# max30105_iiT.net
KiCad netlist of a schematic drawn in EAGLE
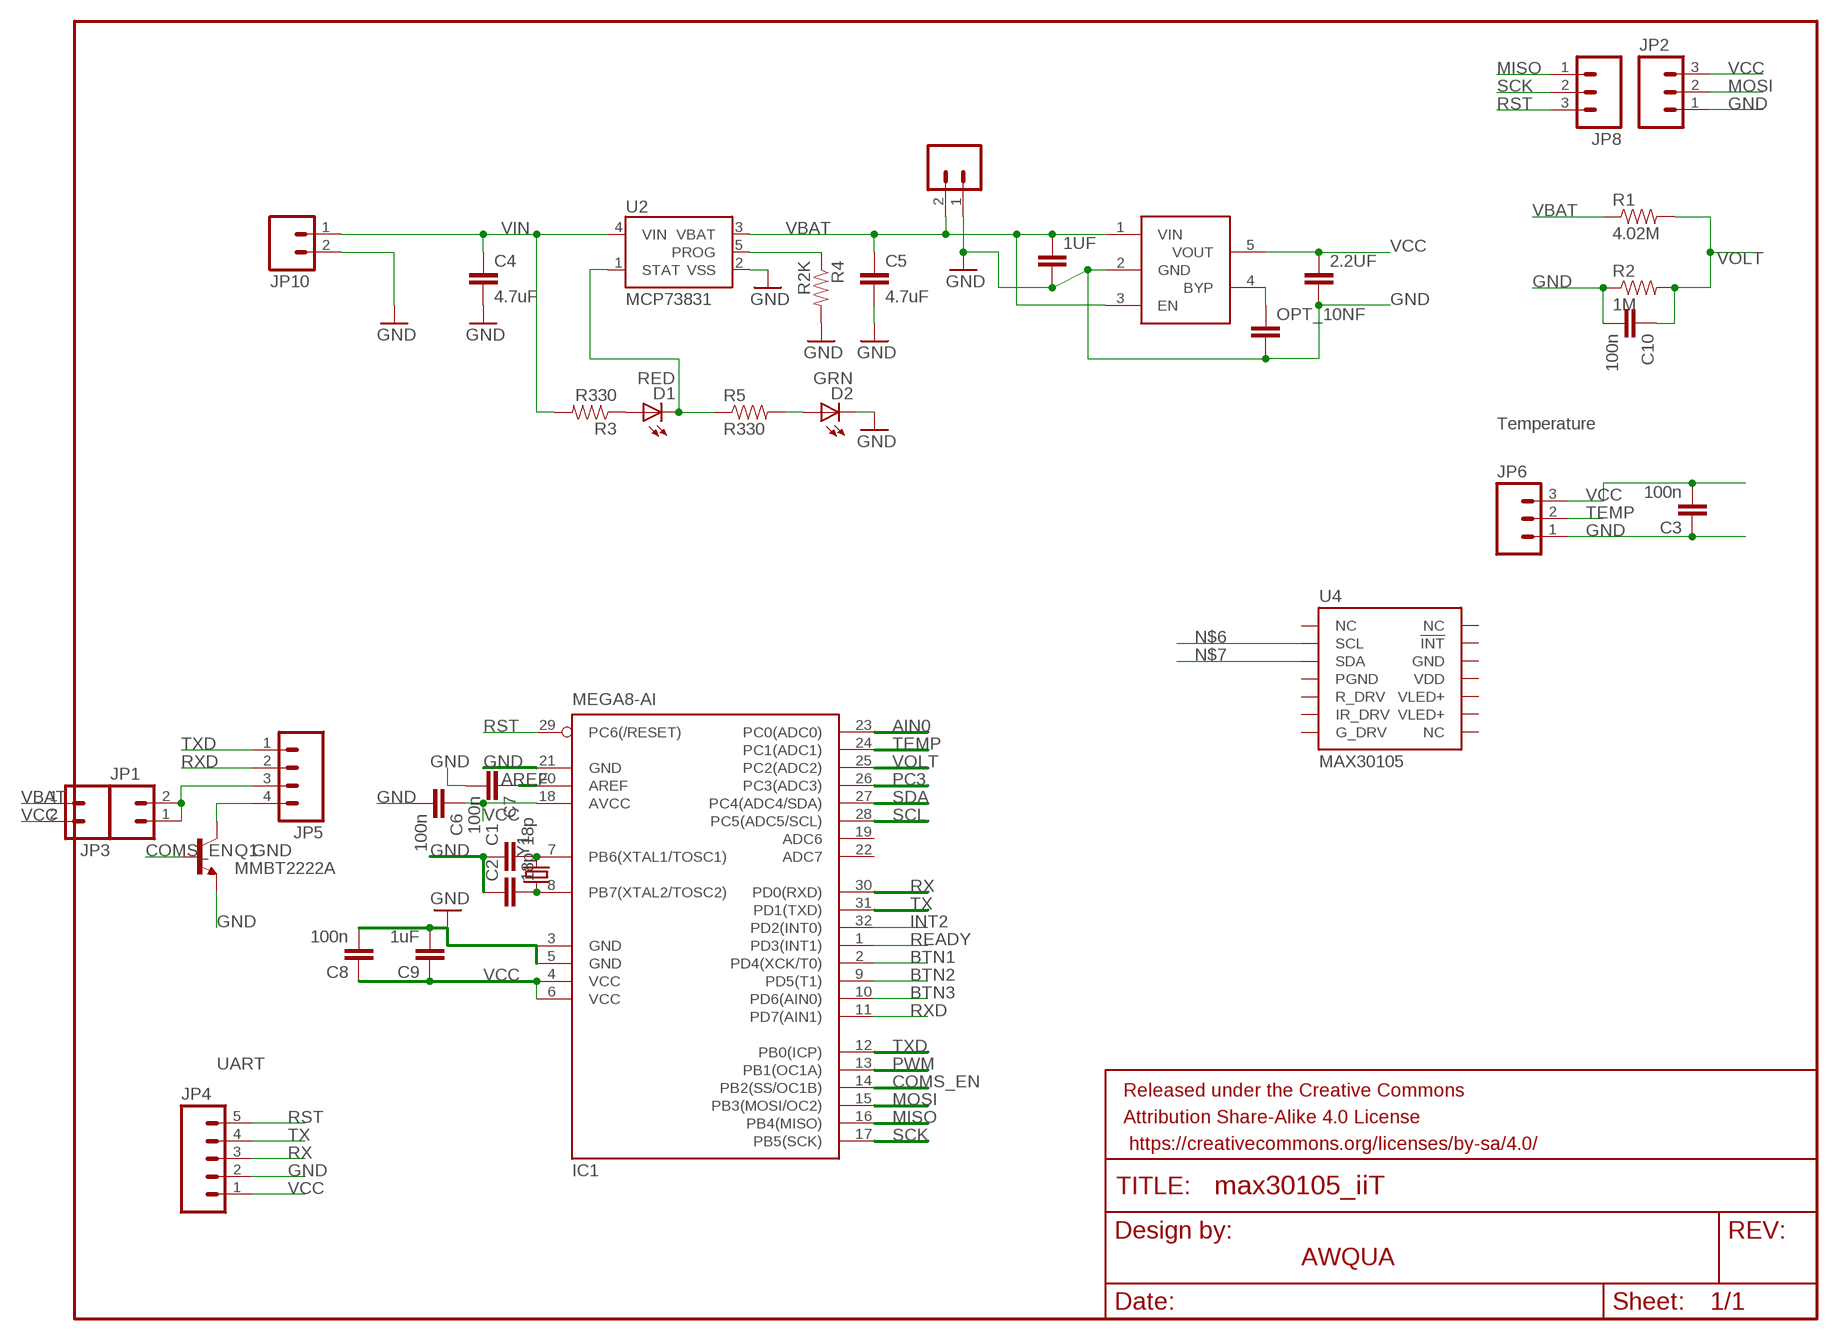
[diagram p0: schematic, sheet 1]

(export (version "E")
  (design (tool "Eeschema 10.0.6"))
  (components
    (comp (ref "1UF")
      (value "CAP0603-CAP")
      (footprint "eagle-import:0603-CAP")
      (libsource (lib "eagle-import") (part "SparkFun-Passives_CAP0603-CAP"))
    )
    (comp (ref "2.2UF")
      (value "CAP0603-CAP")
      (footprint "eagle-import:0603-CAP")
      (libsource (lib "eagle-import") (part "SparkFun-Passives_CAP0603-CAP"))
    )
    (comp (ref "C1")
      (value "18p")
      (footprint "eagle-import:0603-CAP")
      (libsource (lib "eagle-import") (part "CAP0603-CAP"))
    )
    (comp (ref "C2")
      (value "18p")
      (footprint "eagle-import:0603-CAP")
      (libsource (lib "eagle-import") (part "CAP0603-CAP"))
    )
    (comp (ref "C3")
      (value "100n")
      (footprint "eagle-import:0603-CAP")
      (libsource (lib "eagle-import") (part "CAP0603-CAP"))
    )
    (comp (ref "C4")
      (value "4.7uF")
      (footprint "eagle-import:0402-CAP")
      (libsource (lib "eagle-import") (part "CAP0402-CAP"))
    )
    (comp (ref "C5")
      (value "4.7uF")
      (footprint "eagle-import:0402-CAP")
      (libsource (lib "eagle-import") (part "CAP0402-CAP"))
    )
    (comp (ref "C6")
      (value "100n")
      (footprint "eagle-import:0603-CAP")
      (libsource (lib "eagle-import") (part "CAP0603-CAP"))
    )
    (comp (ref "C7")
      (value "100n")
      (footprint "eagle-import:0603-CAP")
      (libsource (lib "eagle-import") (part "CAP0603-CAP"))
    )
    (comp (ref "C8")
      (value "100n")
      (footprint "eagle-import:0603-CAP")
      (libsource (lib "eagle-import") (part "CAP0603-CAP"))
    )
    (comp (ref "C9")
      (value "1uF")
      (footprint "eagle-import:0603-CAP")
      (libsource (lib "eagle-import") (part "CAP0603-CAP"))
    )
    (comp (ref "C10")
      (value "100n")
      (footprint "eagle-import:0603-CAP")
      (libsource (lib "eagle-import") (part "CAP0603-CAP"))
    )
    (comp (ref "D1")
      (value "RED")
      (footprint "eagle-import:LED-0603")
      (libsource (lib "eagle-import") (part "LED0603"))
    )
    (comp (ref "D2")
      (value "GRN")
      (footprint "eagle-import:LED-0603")
      (libsource (lib "eagle-import") (part "LED0603"))
    )
    (comp (ref "FRAME1")
      (value "FRAME-LETTER")
      (footprint "eagle-import:CREATIVE_COMMONS")
      (libsource (lib "eagle-import") (part "FRAME-LETTER"))
    )
    (comp (ref "IC1")
      (value "MEGA8-AI")
      (footprint "eagle-import:TQFP32-08")
      (fields (field (name "MPN") "ATMEGA8-16AU"))
      (libsource (lib "eagle-import") (part "MEGA8-AI"))
    )
    (comp (ref "JP1")
      (value "M02PTH")
      (footprint "eagle-import:1X02")
      (libsource (lib "eagle-import") (part "SparkFun-Connectors_M02PTH"))
    )
    (comp (ref "JP2")
      (value "M03PTH")
      (footprint "eagle-import:1X03")
      (libsource (lib "eagle-import") (part "M03PTH"))
    )
    (comp (ref "JP3")
      (value "M02PTH")
      (footprint "eagle-import:1X02")
      (libsource (lib "eagle-import") (part "SparkFun-Connectors_M02PTH"))
    )
    (comp (ref "JP4")
      (value "M05PTH")
      (footprint "eagle-import:1X05")
      (libsource (lib "eagle-import") (part "M05PTH"))
    )
    (comp (ref "JP5")
      (value "M04PTH")
      (footprint "eagle-import:1X04")
      (libsource (lib "eagle-import") (part "M04PTH"))
    )
    (comp (ref "JP6")
      (value "M03PTH")
      (footprint "eagle-import:1X03")
      (libsource (lib "eagle-import") (part "M03PTH"))
    )
    (comp (ref "JP7")
      (value "LiPo Battery")
      (footprint "eagle-import:JST-2-SMD")
      (libsource (lib "eagle-import") (part "M02-JST-2MM-SMT"))
    )
    (comp (ref "JP8")
      (value "M03PTH")
      (footprint "eagle-import:1X03")
      (libsource (lib "eagle-import") (part "M03PTH"))
    )
    (comp (ref "JP10")
      (value "M02PTH")
      (footprint "eagle-import:1X02")
      (libsource (lib "eagle-import") (part "SparkFun-Connectors_M02PTH"))
    )
    (comp (ref "OPT_10NF")
      (value "CAP0603-CAP")
      (footprint "eagle-import:0603-CAP")
      (libsource (lib "eagle-import") (part "SparkFun-Passives_CAP0603-CAP"))
    )
    (comp (ref "Q1")
      (value "MMBT2222A")
      (footprint "eagle-import:SOT23-3")
      (libsource (lib "eagle-import") (part "TRANSISTOR_NPNMMBT2222A"))
    )
    (comp (ref "R1")
      (value "4.02M")
      (footprint "eagle-import:0603-RES")
      (libsource (lib "eagle-import") (part "RESISTOR0603"))
    )
    (comp (ref "R2")
      (value "1M")
      (footprint "eagle-import:0603-RES")
      (libsource (lib "eagle-import") (part "RESISTOR0603"))
    )
    (comp (ref "R3")
      (value "R330")
      (footprint "eagle-import:0402-RES")
      (libsource (lib "eagle-import") (part "RESISTOR0402-RES"))
    )
    (comp (ref "R4")
      (value "R2K")
      (footprint "eagle-import:0402-RES")
      (libsource (lib "eagle-import") (part "RESISTOR0402-RES"))
    )
    (comp (ref "R5")
      (value "R330")
      (footprint "eagle-import:0402-RES")
      (libsource (lib "eagle-import") (part "RESISTOR0402-RES"))
    )
    (comp (ref "U$6")
      (value "LP2985")
      (footprint "eagle-import:LP2985")
      (libsource (lib "eagle-import") (part "LP2985"))
    )
    (comp (ref "U2")
      (value "MCP73831")
      (footprint "eagle-import:SOT23-5")
      (libsource (lib "eagle-import") (part "MCP73831"))
    )
    (comp (ref "U4")
      (value "MAX30105")
      (footprint "eagle-import:OLGA-14")
      (libsource (lib "eagle-import") (part "MAX30105SMD"))
    )
    (comp (ref "Y1")
      (value "CRYSTAL5X3")
      (footprint "eagle-import:CRYSTAL-SMD-5X3")
      (libsource (lib "eagle-import") (part "CRYSTAL5X3"))
    )
  )
  (nets
    (net (code "1") (name "/AIN0") (class "Default")
      (node (ref "IC1") (pin "23") (pinfunction "PC0(ADC0)_23") (pintype "bidirectional"))
    )
    (net (code "2") (name "/AREF") (class "Default")
      (node (ref "C7") (pin "1") (pinfunction "1_1") (pintype "passive"))
      (node (ref "IC1") (pin "20") (pinfunction "AREF_20") (pintype "passive"))
    )
    (net (code "3") (name "/BTN1") (class "Default")
      (node (ref "IC1") (pin "2") (pinfunction "PD4(XCK/T0)_2") (pintype "bidirectional"))
    )
    (net (code "4") (name "/BTN2") (class "Default")
      (node (ref "IC1") (pin "9") (pinfunction "PD5(T1)_9") (pintype "bidirectional"))
    )
    (net (code "5") (name "/BTN3") (class "Default")
      (node (ref "IC1") (pin "10") (pinfunction "PD6(AIN0)_10") (pintype "bidirectional"))
    )
    (net (code "6") (name "/COMS_EN") (class "Default")
      (node (ref "IC1") (pin "14") (pinfunction "PB2(SS/OC1B)_14") (pintype "bidirectional"))
      (node (ref "Q1") (pin "1") (pinfunction "B_1") (pintype "passive"))
    )
    (net (code "7") (name "/INT2") (class "Default")
      (node (ref "IC1") (pin "32") (pinfunction "PD2(INT0)_32") (pintype "bidirectional"))
    )
    (net (code "8") (name "/MISO") (class "Default")
      (node (ref "IC1") (pin "16") (pinfunction "PB4(MISO)_16") (pintype "bidirectional"))
      (node (ref "JP8") (pin "1") (pinfunction "1_1") (pintype "passive"))
    )
    (net (code "9") (name "/MOSI") (class "Default")
      (node (ref "IC1") (pin "15") (pinfunction "PB3(MOSI/OC2)_15") (pintype "bidirectional"))
      (node (ref "JP2") (pin "2") (pinfunction "2_2") (pintype "passive"))
    )
    (net (code "10") (name "/N$6") (class "Default")
      (node (ref "U4") (pin "2") (pinfunction "SCL_2") (pintype "bidirectional"))
    )
    (net (code "11") (name "/N$7") (class "Default")
      (node (ref "U4") (pin "3") (pinfunction "SDA_3") (pintype "bidirectional"))
    )
    (net (code "12") (name "/PC3") (class "Default")
      (node (ref "IC1") (pin "26") (pinfunction "PC3(ADC3)_26") (pintype "bidirectional"))
    )
    (net (code "13") (name "/PWM") (class "Default")
      (node (ref "IC1") (pin "13") (pinfunction "PB1(OC1A)_13") (pintype "bidirectional"))
    )
    (net (code "14") (name "/READY") (class "Default")
      (node (ref "IC1") (pin "1") (pinfunction "PD3(INT1)_1") (pintype "bidirectional"))
    )
    (net (code "15") (name "/RST") (class "Default")
      (node (ref "IC1") (pin "29") (pinfunction "PC6(/RESET)_29") (pintype "bidirectional"))
      (node (ref "JP4") (pin "5") (pinfunction "5_5") (pintype "passive"))
      (node (ref "JP8") (pin "3") (pinfunction "3_3") (pintype "passive"))
    )
    (net (code "16") (name "/RX") (class "Default")
      (node (ref "IC1") (pin "30") (pinfunction "PD0(RXD)_30") (pintype "bidirectional"))
      (node (ref "JP4") (pin "3") (pinfunction "3_3") (pintype "passive"))
    )
    (net (code "17") (name "/RXD") (class "Default")
      (node (ref "IC1") (pin "11") (pinfunction "PD7(AIN1)_11") (pintype "bidirectional"))
      (node (ref "JP5") (pin "2") (pinfunction "2_2") (pintype "passive"))
    )
    (net (code "18") (name "/SCK") (class "Default")
      (node (ref "IC1") (pin "17") (pinfunction "PB5(SCK)_17") (pintype "bidirectional"))
      (node (ref "JP8") (pin "2") (pinfunction "2_2") (pintype "passive"))
    )
    (net (code "19") (name "/SCL") (class "Default")
      (node (ref "IC1") (pin "28") (pinfunction "PC5(ADC5/SCL)_28") (pintype "bidirectional"))
    )
    (net (code "20") (name "/SDA") (class "Default")
      (node (ref "IC1") (pin "27") (pinfunction "PC4(ADC4/SDA)_27") (pintype "bidirectional"))
    )
    (net (code "21") (name "/TEMP") (class "Default")
      (node (ref "IC1") (pin "24") (pinfunction "PC1(ADC1)_24") (pintype "bidirectional"))
      (node (ref "JP6") (pin "2") (pinfunction "2_2") (pintype "passive"))
    )
    (net (code "22") (name "/TX") (class "Default")
      (node (ref "IC1") (pin "31") (pinfunction "PD1(TXD)_31") (pintype "bidirectional"))
      (node (ref "JP4") (pin "4") (pinfunction "4_4") (pintype "passive"))
    )
    (net (code "23") (name "/TXD") (class "Default")
      (node (ref "IC1") (pin "12") (pinfunction "PB0(ICP)_12") (pintype "bidirectional"))
      (node (ref "JP5") (pin "1") (pinfunction "1_1") (pintype "passive"))
    )
    (net (code "24") (name "/VBAT") (class "Default")
      (node (ref "1UF") (pin "1") (pinfunction "1_1") (pintype "passive"))
      (node (ref "C5") (pin "1") (pinfunction "1_1") (pintype "passive"))
      (node (ref "JP3") (pin "1") (pinfunction "1_1") (pintype "passive"))
      (node (ref "JP7") (pin "2") (pinfunction "2_2") (pintype "passive"))
      (node (ref "R1") (pin "1") (pinfunction "1_1") (pintype "passive"))
      (node (ref "U$6") (pin "1") (pinfunction "VIN_1") (pintype "bidirectional"))
      (node (ref "U$6") (pin "3") (pinfunction "EN_3") (pintype "bidirectional"))
      (node (ref "U2") (pin "3") (pinfunction "VBAT_3") (pintype "power_in"))
    )
    (net (code "25") (name "/VCC") (class "Default")
      (node (ref "2.2UF") (pin "1") (pinfunction "1_1") (pintype "passive"))
      (node (ref "C3") (pin "2") (pinfunction "2_2") (pintype "passive"))
      (node (ref "C6") (pin "1") (pinfunction "1_1") (pintype "passive"))
      (node (ref "C8") (pin "1") (pinfunction "1_1") (pintype "passive"))
      (node (ref "C9") (pin "1") (pinfunction "1_1") (pintype "passive"))
      (node (ref "IC1") (pin "18") (pinfunction "AVCC_18") (pintype "power_in"))
      (node (ref "IC1") (pin "4") (pinfunction "VCC_4") (pintype "power_in"))
      (node (ref "IC1") (pin "6") (pinfunction "VCC_6") (pintype "power_in"))
      (node (ref "JP2") (pin "3") (pinfunction "3_3") (pintype "passive"))
      (node (ref "JP3") (pin "2") (pinfunction "2_2") (pintype "passive"))
      (node (ref "JP4") (pin "1") (pinfunction "1_1") (pintype "passive"))
      (node (ref "JP6") (pin "3") (pinfunction "3_3") (pintype "passive"))
      (node (ref "U$6") (pin "5") (pinfunction "VOUT_5") (pintype "bidirectional"))
    )
    (net (code "26") (name "/VIN") (class "Default")
      (node (ref "C4") (pin "1") (pinfunction "1_1") (pintype "passive"))
      (node (ref "JP10") (pin "1") (pinfunction "1_1") (pintype "passive"))
      (node (ref "R3") (pin "2") (pinfunction "2_2") (pintype "passive"))
      (node (ref "U2") (pin "4") (pinfunction "VIN_4") (pintype "power_in"))
    )
    (net (code "27") (name "/VOLT") (class "Default")
      (node (ref "C10") (pin "1") (pinfunction "1_1") (pintype "passive"))
      (node (ref "IC1") (pin "25") (pinfunction "PC2(ADC2)_25") (pintype "bidirectional"))
      (node (ref "R1") (pin "2") (pinfunction "2_2") (pintype "passive"))
      (node (ref "R2") (pin "2") (pinfunction "2_2") (pintype "passive"))
    )
    (net (code "28") (name "GND") (class "Default")
      (node (ref "1UF") (pin "2") (pinfunction "2_2") (pintype "passive"))
      (node (ref "2.2UF") (pin "2") (pinfunction "2_2") (pintype "passive"))
      (node (ref "C1") (pin "1") (pinfunction "1_1") (pintype "passive"))
      (node (ref "C10") (pin "2") (pinfunction "2_2") (pintype "passive"))
      (node (ref "C2") (pin "1") (pinfunction "1_1") (pintype "passive"))
      (node (ref "C3") (pin "1") (pinfunction "1_1") (pintype "passive"))
      (node (ref "C4") (pin "2") (pinfunction "2_2") (pintype "passive"))
      (node (ref "C5") (pin "2") (pinfunction "2_2") (pintype "passive"))
      (node (ref "C6") (pin "2") (pinfunction "2_2") (pintype "passive"))
      (node (ref "C7") (pin "2") (pinfunction "2_2") (pintype "passive"))
      (node (ref "C8") (pin "2") (pinfunction "2_2") (pintype "passive"))
      (node (ref "C9") (pin "2") (pinfunction "2_2") (pintype "passive"))
      (node (ref "D2") (pin "C") (pinfunction "C_C") (pintype "passive"))
      (node (ref "IC1") (pin "21") (pinfunction "GND_21") (pintype "power_in"))
      (node (ref "IC1") (pin "3") (pinfunction "GND_3") (pintype "power_in"))
      (node (ref "IC1") (pin "5") (pinfunction "GND_5") (pintype "power_in"))
      (node (ref "JP10") (pin "2") (pinfunction "2_2") (pintype "passive"))
      (node (ref "JP2") (pin "1") (pinfunction "1_1") (pintype "passive"))
      (node (ref "JP4") (pin "2") (pinfunction "2_2") (pintype "passive"))
      (node (ref "JP5") (pin "4") (pinfunction "4_4") (pintype "passive"))
      (node (ref "JP6") (pin "1") (pinfunction "1_1") (pintype "passive"))
      (node (ref "JP7") (pin "1") (pinfunction "1_1") (pintype "passive"))
      (node (ref "OPT_10NF") (pin "2") (pinfunction "2_2") (pintype "passive"))
      (node (ref "Q1") (pin "2") (pinfunction "E_2") (pintype "passive"))
      (node (ref "Q1") (pin "3") (pinfunction "C_3") (pintype "passive"))
      (node (ref "R2") (pin "1") (pinfunction "1_1") (pintype "passive"))
      (node (ref "R4") (pin "2") (pinfunction "2_2") (pintype "passive"))
      (node (ref "U$6") (pin "2") (pinfunction "GND_2") (pintype "bidirectional"))
      (node (ref "U2") (pin "2") (pinfunction "VSS_2") (pintype "power_in"))
    )
    (net (code "29") (name "Net-(D1-PadA)") (class "Default")
      (node (ref "D1") (pin "A") (pinfunction "A_A") (pintype "passive"))
      (node (ref "R3") (pin "1") (pinfunction "1_1") (pintype "passive"))
    )
    (net (code "30") (name "Net-(D2-PadA)") (class "Default")
      (node (ref "D2") (pin "A") (pinfunction "A_A") (pintype "passive"))
      (node (ref "R5") (pin "2") (pinfunction "2_2") (pintype "passive"))
    )
    (net (code "31") (name "Net-(IC1-PB6(XTAL1{slash}TOSC1))") (class "Default")
      (node (ref "C1") (pin "2") (pinfunction "2_2") (pintype "passive"))
      (node (ref "IC1") (pin "7") (pinfunction "PB6(XTAL1/TOSC1)_7") (pintype "bidirectional"))
      (node (ref "Y1") (pin "3") (pinfunction "2_3") (pintype "passive"))
    )
    (net (code "32") (name "Net-(IC1-PB7(XTAL2{slash}TOSC2))") (class "Default")
      (node (ref "C2") (pin "2") (pinfunction "2_2") (pintype "passive"))
      (node (ref "IC1") (pin "8") (pinfunction "PB7(XTAL2/TOSC2)_8") (pintype "bidirectional"))
      (node (ref "Y1") (pin "1") (pinfunction "1_1") (pintype "passive"))
    )
    (net (code "33") (name "Net-(JP1-Pad1)") (class "Default")
      (node (ref "JP1") (pin "1") (pinfunction "1_1") (pintype "passive"))
      (node (ref "JP1") (pin "2") (pinfunction "2_2") (pintype "passive"))
      (node (ref "JP5") (pin "3") (pinfunction "3_3") (pintype "passive"))
    )
    (net (code "34") (name "Net-(U$6-BYP)") (class "Default")
      (node (ref "OPT_10NF") (pin "1") (pinfunction "1_1") (pintype "passive"))
      (node (ref "U$6") (pin "4") (pinfunction "BYP_4") (pintype "bidirectional"))
    )
    (net (code "35") (name "Net-(U2-PROG)") (class "Default")
      (node (ref "R4") (pin "1") (pinfunction "1_1") (pintype "passive"))
      (node (ref "U2") (pin "5") (pinfunction "PROG_5") (pintype "input"))
    )
    (net (code "36") (name "Net-(U2-STAT)") (class "Default")
      (node (ref "D1") (pin "C") (pinfunction "C_C") (pintype "passive"))
      (node (ref "R5") (pin "1") (pinfunction "1_1") (pintype "passive"))
      (node (ref "U2") (pin "1") (pinfunction "STAT_1") (pintype "output"))
    )
    (net (code "37") (name "unconnected-(IC1-ADC6-Pad19)") (class "Default")
      (node (ref "IC1") (pin "19") (pinfunction "ADC6_19") (pintype "bidirectional"))
    )
    (net (code "38") (name "unconnected-(IC1-ADC7-Pad22)") (class "Default")
      (node (ref "IC1") (pin "22") (pinfunction "ADC7_22") (pintype "bidirectional"))
    )
    (net (code "39") (name "unconnected-(U4-GND-Pad12)") (class "Default")
      (node (ref "U4") (pin "12") (pinfunction "GND_12") (pintype "bidirectional"))
    )
    (net (code "40") (name "unconnected-(U4-G_DRV-Pad7)") (class "Default")
      (node (ref "U4") (pin "7") (pinfunction "G_DRV_7") (pintype "bidirectional"))
    )
    (net (code "41") (name "unconnected-(U4-IR_DRV-Pad6)") (class "Default")
      (node (ref "U4") (pin "6") (pinfunction "IR_DRV_6") (pintype "bidirectional"))
    )
    (net (code "42") (name "unconnected-(U4-NC-Pad1)") (class "Default")
      (node (ref "U4") (pin "1") (pinfunction "NC_1") (pintype "bidirectional"))
    )
    (net (code "43") (name "unconnected-(U4-NC-Pad8)") (class "Default")
      (node (ref "U4") (pin "8") (pinfunction "NC_8") (pintype "bidirectional"))
    )
    (net (code "44") (name "unconnected-(U4-NC-Pad14)") (class "Default")
      (node (ref "U4") (pin "14") (pinfunction "NC_14") (pintype "bidirectional"))
    )
    (net (code "45") (name "unconnected-(U4-PGND-Pad4)") (class "Default")
      (node (ref "U4") (pin "4") (pinfunction "PGND_4") (pintype "bidirectional"))
    )
    (net (code "46") (name "unconnected-(U4-R_DRV-Pad5)") (class "Default")
      (node (ref "U4") (pin "5") (pinfunction "R_DRV_5") (pintype "bidirectional"))
    )
    (net (code "47") (name "unconnected-(U4-VDD-Pad11)") (class "Default")
      (node (ref "U4") (pin "11") (pinfunction "VDD_11") (pintype "bidirectional"))
    )
    (net (code "48") (name "unconnected-(U4-VLED+-Pad9)") (class "Default")
      (node (ref "U4") (pin "9") (pinfunction "VLED+_9") (pintype "bidirectional"))
    )
    (net (code "49") (name "unconnected-(U4-VLED+-Pad10)") (class "Default")
      (node (ref "U4") (pin "10") (pinfunction "VLED+_10") (pintype "bidirectional"))
    )
    (net (code "50") (name "unconnected-(U4-~{INT}-Pad13)") (class "Default")
      (node (ref "U4") (pin "13") (pinfunction "~{INT}_13") (pintype "bidirectional"))
    )
  )
)
